# Enclosure_85x58_PBW.net
KiCad netlist of a schematic drawn in EAGLE
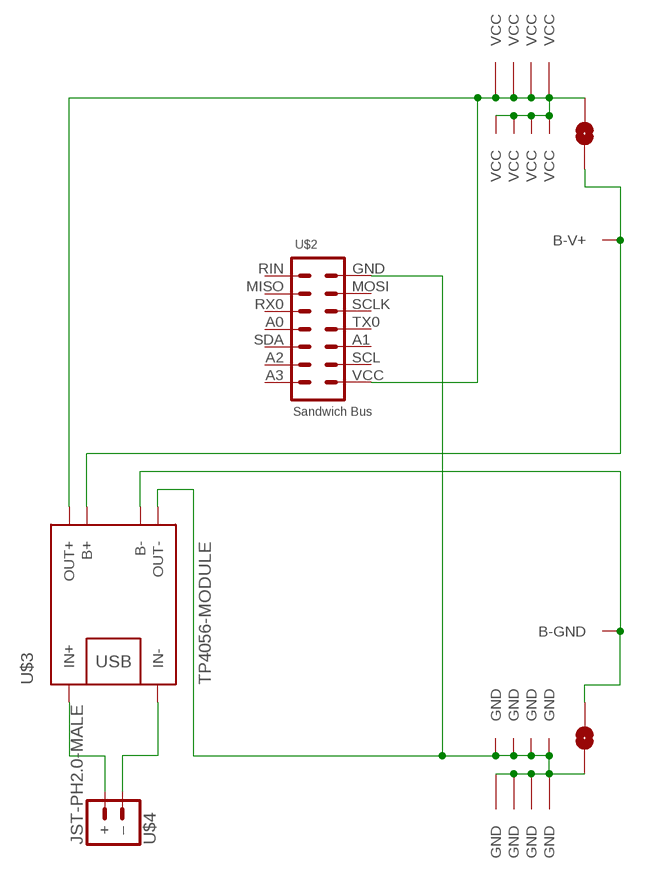
[diagram p0: schematic, sheet 1]

(export (version "E")
  (design (tool "Eeschema 10.0.6"))
  (components
    (comp (ref "U$1")
      (value "PROTO-28X18-BAT2-SJ-W")
      (footprint "eagle-import:PROTO-28X18-BAT2-SJ-W")
      (libsource (lib "eagle-import") (part "PROTO-28X18-BAT2-SJ-W"))
    )
    (comp (ref "U$2")
      (value "Sandwich Bus")
      (footprint "eagle-import:CONN_2X7-WIJNAND-PROCESSOR")
      (libsource (lib "eagle-import") (part "2X7-WIJNAND-PROCESSOR-HEADER"))
    )
    (comp (ref "U$3")
      (value "TP4056-MODULE")
      (footprint "eagle-import:BATTERY-CHARGER-LI-PROT")
      (libsource (lib "eagle-import") (part "TP4056-MODULE"))
    )
    (comp (ref "U$4")
      (value "JST-PH2.0-MALE")
      (footprint "eagle-import:JST-PH2.0")
      (libsource (lib "eagle-import") (part "JST-PH2.0-MALE"))
    )
  )
  (nets
    (net (code "1") (name "Net-(U$1-B-GND-PadB-GND@SJ)") (class "Default")
      (node (ref "U$1") (pin "B-GND@SJ") (pinfunction "B-GND_B-GND@SJ") (pintype "power_in"))
      (node (ref "U$1") (pin "P25-16") (pinfunction "B-GND_P25-16") (pintype "power_in"))
      (node (ref "U$3") (pin "B-") (pinfunction "B-_B-") (pintype "power_in"))
    )
    (net (code "2") (name "Net-(U$1-B-V+-PadB-V+@SJ)") (class "Default")
      (node (ref "U$1") (pin "B-V+@SJ") (pinfunction "B-V+_B-V+@SJ") (pintype "power_in"))
      (node (ref "U$1") (pin "P03-16") (pinfunction "B-V+_P03-16") (pintype "power_in"))
      (node (ref "U$3") (pin "B+") (pinfunction "B+_B+") (pintype "power_in"))
    )
    (net (code "3") (name "Net-(U$2-1)") (class "Default")
      (node (ref "U$1") (pin "P01-11") (pinfunction "VCC_P01-11") (pintype "power_in"))
      (node (ref "U$1") (pin "P01-12") (pinfunction "VCC_P01-12") (pintype "power_in"))
      (node (ref "U$1") (pin "P01-13") (pinfunction "VCC_P01-13") (pintype "power_in"))
      (node (ref "U$1") (pin "P01-14") (pinfunction "VCC_P01-14") (pintype "power_in"))
      (node (ref "U$1") (pin "P02-11") (pinfunction "VCC_P02-11") (pintype "power_in"))
      (node (ref "U$1") (pin "P02-12") (pinfunction "VCC_P02-12") (pintype "power_in"))
      (node (ref "U$1") (pin "P02-13") (pinfunction "VCC_P02-13") (pintype "power_in"))
      (node (ref "U$1") (pin "P02-14") (pinfunction "VCC_P02-14") (pintype "bidirectional"))
      (node (ref "U$1") (pin "VCC@SJ") (pinfunction "VCC_VCC@SJ") (pintype "power_in"))
      (node (ref "U$2") (pin "VCC") (pinfunction "1_VCC") (pintype "passive"))
      (node (ref "U$3") (pin "OUT+") (pinfunction "OUT+_OUT+") (pintype "power_in"))
    )
    (net (code "4") (name "Net-(U$2-7)") (class "Default")
      (node (ref "U$1") (pin "GND@SJ") (pinfunction "GND_GND@SJ") (pintype "power_in"))
      (node (ref "U$1") (pin "P27-11") (pinfunction "GND_P27-11") (pintype "power_in"))
      (node (ref "U$1") (pin "P27-12") (pinfunction "GND_P27-12") (pintype "power_in"))
      (node (ref "U$1") (pin "P27-13") (pinfunction "GND_P27-13") (pintype "power_in"))
      (node (ref "U$1") (pin "P27-14") (pinfunction "GND_P27-14") (pintype "bidirectional"))
      (node (ref "U$1") (pin "P28-11") (pinfunction "GND_P28-11") (pintype "power_in"))
      (node (ref "U$1") (pin "P28-12") (pinfunction "GND_P28-12") (pintype "power_in"))
      (node (ref "U$1") (pin "P28-13") (pinfunction "GND_P28-13") (pintype "power_in"))
      (node (ref "U$1") (pin "P28-14") (pinfunction "GND_P28-14") (pintype "power_in"))
      (node (ref "U$2") (pin "GND") (pinfunction "7_GND") (pintype "passive"))
      (node (ref "U$3") (pin "OUT-") (pinfunction "OUT-_OUT-") (pintype "power_in"))
    )
    (net (code "5") (name "Net-(U$3-PadIN+)") (class "Default")
      (node (ref "U$3") (pin "IN+") (pinfunction "IN+_IN+") (pintype "power_in"))
      (node (ref "U$4") (pin "+") (pinfunction "+_+") (pintype "power_in"))
    )
    (net (code "6") (name "Net-(U$4-–)") (class "Default")
      (node (ref "U$3") (pin "IN-") (pinfunction "IN-_IN-") (pintype "power_in"))
      (node (ref "U$4") (pin "-") (pinfunction "–_-") (pintype "power_in"))
    )
    (net (code "7") (name "unconnected-(U$2-2-PadSCL)") (class "Default")
      (node (ref "U$2") (pin "SCL") (pinfunction "2_SCL") (pintype "passive"))
    )
    (net (code "8") (name "unconnected-(U$2-3-PadA1)") (class "Default")
      (node (ref "U$2") (pin "A1") (pinfunction "3_A1") (pintype "passive"))
    )
    (net (code "9") (name "unconnected-(U$2-4-PadTX0)") (class "Default")
      (node (ref "U$2") (pin "TX0") (pinfunction "4_TX0") (pintype "passive"))
    )
    (net (code "10") (name "unconnected-(U$2-5-PadSCLK)") (class "Default")
      (node (ref "U$2") (pin "SCLK") (pinfunction "5_SCLK") (pintype "passive"))
    )
    (net (code "11") (name "unconnected-(U$2-6-PadMOSI)") (class "Default")
      (node (ref "U$2") (pin "MOSI") (pinfunction "6_MOSI") (pintype "passive"))
    )
    (net (code "12") (name "unconnected-(U$2-8-PadRIN)") (class "Default")
      (node (ref "U$2") (pin "RIN") (pinfunction "8_RIN") (pintype "passive"))
    )
    (net (code "13") (name "unconnected-(U$2-9-PadMISO)") (class "Default")
      (node (ref "U$2") (pin "MISO") (pinfunction "9_MISO") (pintype "passive"))
    )
    (net (code "14") (name "unconnected-(U$2-10-PadRX0)") (class "Default")
      (node (ref "U$2") (pin "RX0") (pinfunction "10_RX0") (pintype "passive"))
    )
    (net (code "15") (name "unconnected-(U$2-11-PadA0)") (class "Default")
      (node (ref "U$2") (pin "A0") (pinfunction "11_A0") (pintype "passive"))
    )
    (net (code "16") (name "unconnected-(U$2-12-PadSDA)") (class "Default")
      (node (ref "U$2") (pin "SDA") (pinfunction "12_SDA") (pintype "passive"))
    )
    (net (code "17") (name "unconnected-(U$2-13-PadA2)") (class "Default")
      (node (ref "U$2") (pin "A2") (pinfunction "13_A2") (pintype "passive"))
    )
    (net (code "18") (name "unconnected-(U$2-14-PadA3)") (class "Default")
      (node (ref "U$2") (pin "A3") (pinfunction "14_A3") (pintype "passive"))
    )
  )
)
